# PEC16_straddle.net
KiCad netlist of a schematic drawn in EAGLE
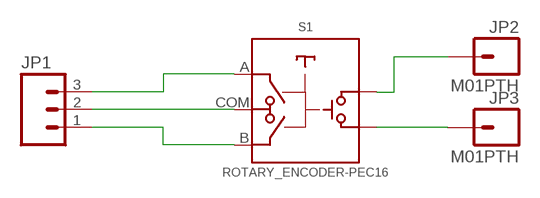
[diagram p0: schematic, sheet 1]

(export (version "E")
  (design (tool "Eeschema 10.0.6"))
  (components
    (comp (ref "JP1")
      (value "M03PTH")
      (footprint "eagle-import:1X03")
      (libsource (lib "eagle-import") (part "M03PTH"))
    )
    (comp (ref "JP2")
      (value "M01PTH")
      (footprint "eagle-import:1X01")
      (libsource (lib "eagle-import") (part "M01PTH"))
    )
    (comp (ref "JP3")
      (value "M01PTH")
      (footprint "eagle-import:1X01")
      (libsource (lib "eagle-import") (part "M01PTH"))
    )
    (comp (ref "S1")
      (value "ROTARY_ENCODER-PEC16")
      (footprint "eagle-import:PEC16-2XXX")
      (libsource (lib "eagle-import") (part "ROTARY_ENCODER-PEC16"))
    )
  )
  (nets
    (net (code "1") (name "Net-(JP1-Pad1)") (class "Default")
      (node (ref "JP1") (pin "1") (pinfunction "1_1") (pintype "passive"))
      (node (ref "S1") (pin "B") (pinfunction "B_B") (pintype "bidirectional"))
    )
    (net (code "2") (name "Net-(JP1-Pad2)") (class "Default")
      (node (ref "JP1") (pin "2") (pinfunction "2_2") (pintype "passive"))
      (node (ref "S1") (pin "COM") (pinfunction "COM_COM") (pintype "bidirectional"))
    )
    (net (code "3") (name "Net-(JP1-Pad3)") (class "Default")
      (node (ref "JP1") (pin "3") (pinfunction "3_3") (pintype "passive"))
      (node (ref "S1") (pin "A") (pinfunction "A_A") (pintype "bidirectional"))
    )
    (net (code "4") (name "Net-(JP2-Pad1)") (class "Default")
      (node (ref "JP2") (pin "1") (pinfunction "1_1") (pintype "passive"))
      (node (ref "S1") (pin "P$4") (pinfunction "P$4_P$4") (pintype "bidirectional"))
    )
    (net (code "5") (name "Net-(JP3-Pad1)") (class "Default")
      (node (ref "JP3") (pin "1") (pinfunction "1_1") (pintype "passive"))
      (node (ref "S1") (pin "P$5") (pinfunction "P$5_P$5") (pintype "bidirectional"))
    )
  )
)
